# squareinator2.net
KiCad netlist of a schematic drawn in EAGLE
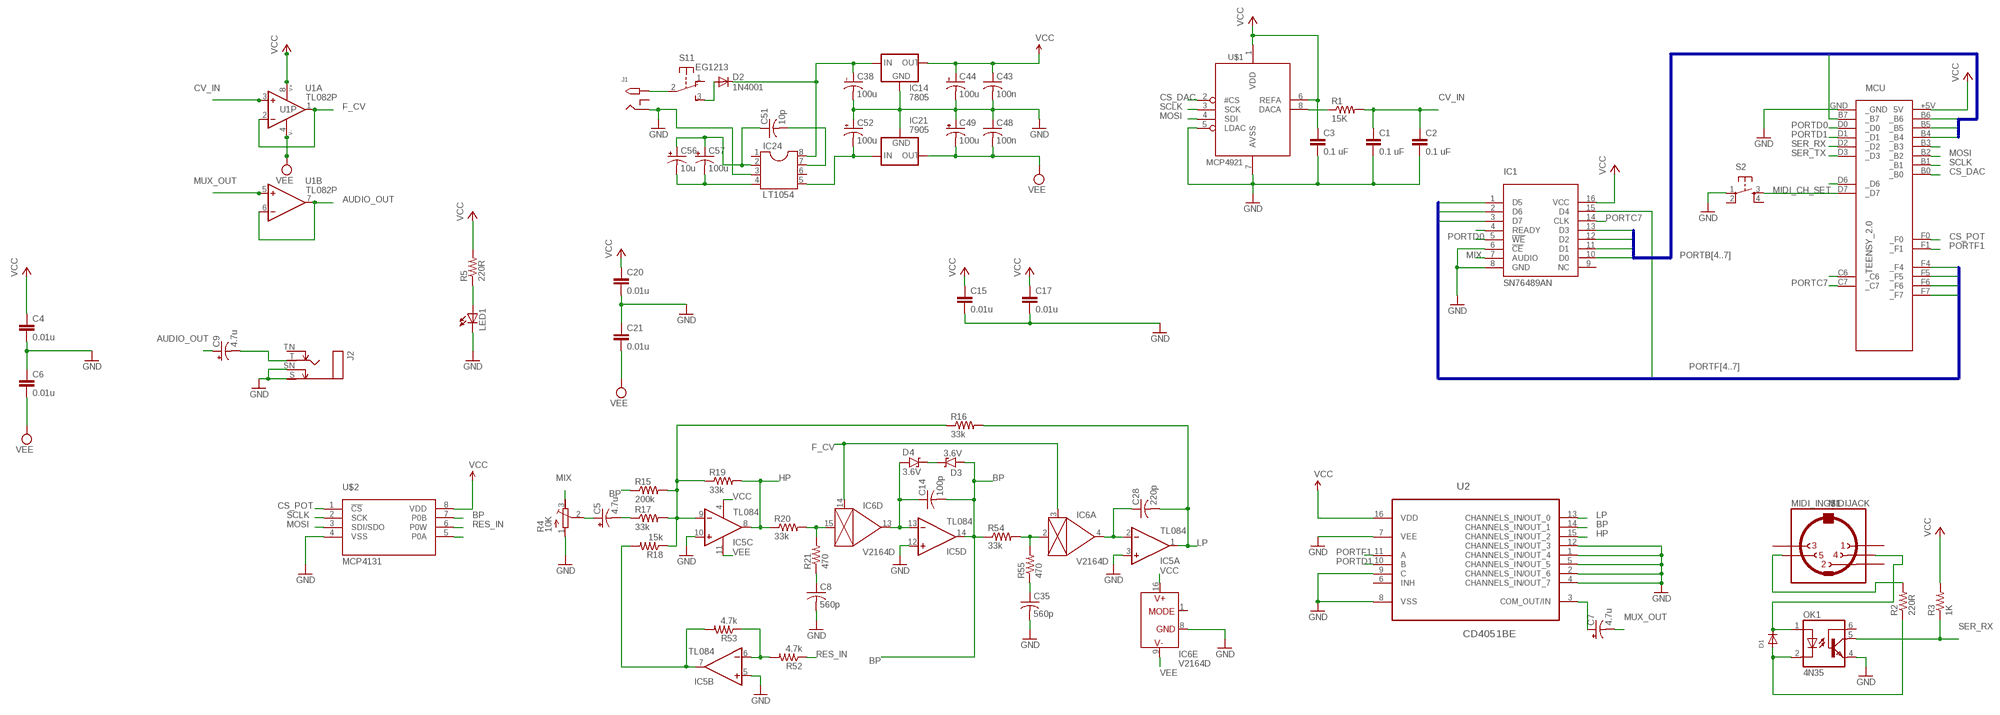
[diagram p0: schematic, sheet 1]

(export (version "E")
  (design (tool "Eeschema 10.0.6"))
  (components
    (comp (ref "C1")
      (value "0.1 uF")
      (footprint "eagle-import:CAP-PTH-SMALLEZ")
      (libsource (lib "eagle-import") (part "CAPEZ"))
    )
    (comp (ref "C2")
      (value "0.1 uF")
      (footprint "eagle-import:CAP-PTH-SMALLEZ")
      (libsource (lib "eagle-import") (part "CAPEZ"))
    )
    (comp (ref "C3")
      (value "0.1 uF")
      (footprint "eagle-import:CAP-PTH-SMALLEZ")
      (libsource (lib "eagle-import") (part "CAPEZ"))
    )
    (comp (ref "C4")
      (value "0.01u")
      (footprint "eagle-import:CAP-PTH-SMALLEZ")
      (libsource (lib "eagle-import") (part "SparkFun-Passives_CAPEZ"))
    )
    (comp (ref "C5")
      (value "4.7u")
      (footprint "eagle-import:E2,5-6")
      (libsource (lib "eagle-import") (part "CPOL-USE2.5-6"))
    )
    (comp (ref "C6")
      (value "0.01u")
      (footprint "eagle-import:CAP-PTH-SMALLEZ")
      (libsource (lib "eagle-import") (part "SparkFun-Passives_CAPEZ"))
    )
    (comp (ref "C7")
      (value "4.7u")
      (footprint "eagle-import:E2,5-6")
      (libsource (lib "eagle-import") (part "CPOL-USE2.5-6"))
    )
    (comp (ref "C8")
      (value "560p")
      (footprint "eagle-import:C025-025X050")
      (libsource (lib "eagle-import") (part "C-US025-025X050"))
    )
    (comp (ref "C9")
      (value "4.7u")
      (footprint "eagle-import:E2,5-6")
      (libsource (lib "eagle-import") (part "CPOL-USE2.5-6"))
    )
    (comp (ref "C14")
      (value "100p")
      (footprint "eagle-import:C025-025X050")
      (libsource (lib "eagle-import") (part "C-US025-025X050"))
    )
    (comp (ref "C15")
      (value "0.01u")
      (footprint "eagle-import:CAP-PTH-SMALLEZ")
      (libsource (lib "eagle-import") (part "SparkFun-Passives_CAPEZ"))
    )
    (comp (ref "C17")
      (value "0.01u")
      (footprint "eagle-import:CAP-PTH-SMALLEZ")
      (libsource (lib "eagle-import") (part "SparkFun-Passives_CAPEZ"))
    )
    (comp (ref "C20")
      (value "0.01u")
      (footprint "eagle-import:CAP-PTH-SMALLEZ")
      (libsource (lib "eagle-import") (part "SparkFun-Passives_CAPEZ"))
    )
    (comp (ref "C21")
      (value "0.01u")
      (footprint "eagle-import:CAP-PTH-SMALLEZ")
      (libsource (lib "eagle-import") (part "SparkFun-Passives_CAPEZ"))
    )
    (comp (ref "C28")
      (value "220p")
      (footprint "eagle-import:C025-025X050")
      (libsource (lib "eagle-import") (part "C-US025-025X050"))
    )
    (comp (ref "C35")
      (value "560p")
      (footprint "eagle-import:C025-025X050")
      (libsource (lib "eagle-import") (part "C-US025-025X050"))
    )
    (comp (ref "C38")
      (value "100u")
      (footprint "eagle-import:E2,5-7")
      (libsource (lib "eagle-import") (part "CPOL-USE2.5-7"))
    )
    (comp (ref "C43")
      (value "100n")
      (footprint "eagle-import:C025-025X050")
      (libsource (lib "eagle-import") (part "C-US025-025X050"))
    )
    (comp (ref "C44")
      (value "100u")
      (footprint "eagle-import:E2,5-7")
      (libsource (lib "eagle-import") (part "CPOL-USE2.5-7"))
    )
    (comp (ref "C48")
      (value "100n")
      (footprint "eagle-import:C025-025X050")
      (libsource (lib "eagle-import") (part "C-US025-025X050"))
    )
    (comp (ref "C49")
      (value "100u")
      (footprint "eagle-import:E2,5-7")
      (libsource (lib "eagle-import") (part "CPOL-USE2.5-7"))
    )
    (comp (ref "C51")
      (value "10p")
      (footprint "eagle-import:C025-025X050")
      (libsource (lib "eagle-import") (part "C-US025-025X050"))
    )
    (comp (ref "C52")
      (value "100u")
      (footprint "eagle-import:E2,5-7")
      (libsource (lib "eagle-import") (part "CPOL-USE2.5-7"))
    )
    (comp (ref "C56")
      (value "10u")
      (footprint "eagle-import:E2,5-5")
      (libsource (lib "eagle-import") (part "CPOL-USE2.5-5"))
    )
    (comp (ref "C57")
      (value "100u")
      (footprint "eagle-import:E2,5-6")
      (libsource (lib "eagle-import") (part "CPOL-USE2.5-6"))
    )
    (comp (ref "D1")
      (value "DIODEDO-1N4148")
      (footprint "eagle-import:DO-1N4148")
      (libsource (lib "eagle-import") (part "DIODEDO-1N4148"))
    )
    (comp (ref "D2")
      (value "1N4001")
      (footprint "eagle-import:DO41-10")
      (libsource (lib "eagle-import") (part "1N4004"))
    )
    (comp (ref "D3")
      (value "3.6V")
      (footprint "eagle-import:D-5")
      (libsource (lib "eagle-import") (part "1N47XXDO35"))
    )
    (comp (ref "D4")
      (value "3.6V")
      (footprint "eagle-import:D-5")
      (libsource (lib "eagle-import") (part "1N47XXDO35"))
    )
    (comp (ref "IC1")
      (value "SN76489AN")
      (footprint "eagle-import:DIL16")
      (libsource (lib "eagle-import") (part "SN76489AN"))
    )
    (comp (ref "IC5")
      (value "TL084")
      (footprint "eagle-import:DIL14")
      (libsource (lib "eagle-import") (part "TL084P"))
    )
    (comp (ref "IC6")
      (value "V2164D")
      (footprint "eagle-import:DIL16")
      (libsource (lib "eagle-import") (part "SSM2164P"))
    )
    (comp (ref "IC14")
      (value "7805")
      (footprint "eagle-import:78XXS")
      (libsource (lib "eagle-import") (part "78XXS"))
    )
    (comp (ref "IC21")
      (value "7905")
      (footprint "eagle-import:79XXS")
      (libsource (lib "eagle-import") (part "79XXS"))
    )
    (comp (ref "IC24")
      (value "LT1054")
      (footprint "eagle-import:DIL08")
      (libsource (lib "eagle-import") (part "DIL8"))
    )
    (comp (ref "J1")
      (value "2.1MMJACKTHM")
      (footprint "eagle-import:PJ-102A")
      (libsource (lib "eagle-import") (part "2.1MMJACKTHM"))
    )
    (comp (ref "J2")
      (value "MONOSWS")
      (footprint "eagle-import:NMJ4HC-S")
      (libsource (lib "eagle-import") (part "MONOSWS"))
    )
    (comp (ref "LED1")
      (value "LED3MM")
      (footprint "eagle-import:LED3MM")
      (libsource (lib "eagle-import") (part "LED3MM"))
    )
    (comp (ref "MCU")
      (value "TEENSY_2.0")
      (footprint "eagle-import:TEENSY")
      (libsource (lib "eagle-import") (part "TEENSYTEENSY_LESSPINS"))
    )
    (comp (ref "MIDI_IN")
      (value "MIDIJACK")
      (footprint "eagle-import:CP-2350")
      (libsource (lib "eagle-import") (part "MIDIJACK"))
    )
    (comp (ref "OK1")
      (value "4N35")
      (footprint "eagle-import:DIL06")
      (fields (field (name "MF") "FAIRCHILD SEMICONDUCTOR"))
      (libsource (lib "eagle-import") (part "4N35"))
    )
    (comp (ref "R1")
      (value "15K")
      (footprint "eagle-import:AXIAL-0.3EZ")
      (libsource (lib "eagle-import") (part "RESISTOREZ"))
    )
    (comp (ref "R2")
      (value "220R")
      (footprint "eagle-import:AXIAL-0.3EZ")
      (libsource (lib "eagle-import") (part "RESISTOREZ"))
    )
    (comp (ref "R3")
      (value "1K")
      (footprint "eagle-import:AXIAL-0.3EZ")
      (libsource (lib "eagle-import") (part "RESISTOREZ"))
    )
    (comp (ref "R4")
      (value "10K")
      (footprint "eagle-import:RTRIM3296P")
      (libsource (lib "eagle-import") (part "R-TRIMM3296P"))
    )
    (comp (ref "R5")
      (value "220R")
      (footprint "eagle-import:AXIAL-0.3EZ")
      (libsource (lib "eagle-import") (part "RESISTOREZ"))
    )
    (comp (ref "R15")
      (value "200k")
      (footprint "eagle-import:0204_7")
      (libsource (lib "eagle-import") (part "R-US_0204/7"))
    )
    (comp (ref "R16")
      (value "33k")
      (footprint "eagle-import:0204_7")
      (libsource (lib "eagle-import") (part "R-US_0204/7"))
    )
    (comp (ref "R17")
      (value "33k")
      (footprint "eagle-import:0204_7")
      (libsource (lib "eagle-import") (part "R-US_0204/7"))
    )
    (comp (ref "R18")
      (value "15k")
      (footprint "eagle-import:0204_7")
      (libsource (lib "eagle-import") (part "R-US_0204/7"))
    )
    (comp (ref "R19")
      (value "33k")
      (footprint "eagle-import:0204_7")
      (libsource (lib "eagle-import") (part "R-US_0204/7"))
    )
    (comp (ref "R20")
      (value "33k")
      (footprint "eagle-import:0204_7")
      (libsource (lib "eagle-import") (part "R-US_0204/7"))
    )
    (comp (ref "R21")
      (value "470")
      (footprint "eagle-import:0204_7")
      (libsource (lib "eagle-import") (part "R-US_0204/7"))
    )
    (comp (ref "R52")
      (value "4.7k")
      (footprint "eagle-import:0204_7")
      (libsource (lib "eagle-import") (part "R-US_0204/7"))
    )
    (comp (ref "R53")
      (value "4.7k")
      (footprint "eagle-import:0204_7")
      (libsource (lib "eagle-import") (part "R-US_0204/7"))
    )
    (comp (ref "R54")
      (value "33k")
      (footprint "eagle-import:0204_7")
      (libsource (lib "eagle-import") (part "R-US_0204/7"))
    )
    (comp (ref "R55")
      (value "470")
      (footprint "eagle-import:0204_7")
      (libsource (lib "eagle-import") (part "R-US_0204/7"))
    )
    (comp (ref "S1")
      (value "EG1213")
      (footprint "eagle-import:EG1213")
      (libsource (lib "eagle-import") (part "EG1213"))
    )
    (comp (ref "S2")
      (value "TAC_SWITCHPTH")
      (footprint "eagle-import:TACTILE-PTH")
      (libsource (lib "eagle-import") (part "TAC_SWITCHPTH"))
    )
    (comp (ref "U$1")
      (value "MCP4921")
      (footprint "eagle-import:DIL08")
      (libsource (lib "eagle-import") (part "MCP4921"))
    )
    (comp (ref "U$2")
      (value "MCP4131")
      (footprint "eagle-import:DIL8")
      (libsource (lib "eagle-import") (part "MCP4131"))
    )
    (comp (ref "U1")
      (value "TL082P")
      (footprint "eagle-import:DIL08")
      (libsource (lib "eagle-import") (part "TL082P"))
    )
    (comp (ref "U2")
      (value "CD4051BE")
      (footprint "eagle-import:DIP254P762X508-16")
      (libsource (lib "eagle-import") (part "CD4051BE"))
    )
  )
  (nets
    (net (code "1") (name "/AUDIO_OUT") (class "Default")
      (node (ref "C9") (pin "+") (pinfunction "+_+") (pintype "passive"))
      (node (ref "U1") (pin "6") (pinfunction "-IN_6") (pintype "input"))
      (node (ref "U1") (pin "7") (pinfunction "OUT_7") (pintype "output"))
    )
    (net (code "2") (name "/BP") (class "Default")
      (node (ref "C14") (pin "2") (pinfunction "2_2") (pintype "passive"))
      (node (ref "D3") (pin "A") (pinfunction "A_A") (pintype "passive"))
      (node (ref "IC5") (pin "14") (pinfunction "OUT_14") (pintype "output"))
      (node (ref "R15") (pin "1") (pinfunction "1_1") (pintype "passive"))
      (node (ref "R54") (pin "1") (pinfunction "1_1") (pintype "passive"))
      (node (ref "U$2") (pin "7") (pinfunction "P0B_7") (pintype "bidirectional"))
      (node (ref "U2") (pin "14") (pinfunction "CHANNELS_IN/OUT_1_14") (pintype "bidirectional"))
    )
    (net (code "3") (name "/CS_DAC") (class "Default")
      (node (ref "MCU") (pin "B0") (pinfunction "_B0_B0") (pintype "bidirectional"))
      (node (ref "U$1") (pin "2") (pinfunction "#CS_2") (pintype "input"))
    )
    (net (code "4") (name "/CS_POT") (class "Default")
      (node (ref "MCU") (pin "F0") (pinfunction "_F0_F0") (pintype "bidirectional"))
      (node (ref "U$2") (pin "1") (pinfunction "~{CS}_1") (pintype "input"))
    )
    (net (code "5") (name "/CV_IN") (class "Default")
      (node (ref "C1") (pin "1") (pinfunction "1_1") (pintype "passive"))
      (node (ref "C2") (pin "1") (pinfunction "1_1") (pintype "passive"))
      (node (ref "R1") (pin "P$2") (pinfunction "2_P$2") (pintype "passive"))
      (node (ref "U1") (pin "3") (pinfunction "+IN_3") (pintype "input"))
    )
    (net (code "6") (name "/F_CV") (class "Default")
      (node (ref "IC6") (pin "14") (pinfunction "CTRL_14") (pintype "input"))
      (node (ref "IC6") (pin "3") (pinfunction "CTRL_3") (pintype "input"))
      (node (ref "U1") (pin "1") (pinfunction "OUT_1") (pintype "output"))
      (node (ref "U1") (pin "2") (pinfunction "-IN_2") (pintype "input"))
    )
    (net (code "7") (name "/HP") (class "Default")
      (node (ref "IC5") (pin "8") (pinfunction "OUT_8") (pintype "output"))
      (node (ref "R19") (pin "2") (pinfunction "2_2") (pintype "passive"))
      (node (ref "R20") (pin "1") (pinfunction "1_1") (pintype "passive"))
      (node (ref "U2") (pin "15") (pinfunction "CHANNELS_IN/OUT_2_15") (pintype "bidirectional"))
    )
    (net (code "8") (name "/LP") (class "Default")
      (node (ref "C28") (pin "2") (pinfunction "2_2") (pintype "passive"))
      (node (ref "IC5") (pin "1") (pinfunction "OUT_1") (pintype "output"))
      (node (ref "R16") (pin "2") (pinfunction "2_2") (pintype "passive"))
      (node (ref "U2") (pin "13") (pinfunction "CHANNELS_IN/OUT_0_13") (pintype "bidirectional"))
    )
    (net (code "9") (name "/MIDI_CH_SET") (class "Default")
      (node (ref "MCU") (pin "D7") (pinfunction "_D7_D7") (pintype "bidirectional"))
      (node (ref "S2") (pin "3") (pinfunction "3_3") (pintype "passive"))
    )
    (net (code "10") (name "/MIX") (class "Default")
      (node (ref "IC1") (pin "7") (pinfunction "AUDIO_7") (pintype "output"))
      (node (ref "R4") (pin "3") (pinfunction "E_3") (pintype "passive"))
    )
    (net (code "11") (name "/MOSI") (class "Default")
      (node (ref "MCU") (pin "B2") (pinfunction "_B2_B2") (pintype "bidirectional"))
      (node (ref "U$1") (pin "4") (pinfunction "SDI_4") (pintype "input"))
      (node (ref "U$2") (pin "3") (pinfunction "SDI/SDO_3") (pintype "bidirectional"))
    )
    (net (code "12") (name "/MUX_OUT") (class "Default")
      (node (ref "C7") (pin "-") (pinfunction "-_-") (pintype "passive"))
      (node (ref "U1") (pin "5") (pinfunction "+IN_5") (pintype "input"))
    )
    (net (code "13") (name "/PORTB4") (class "Default")
      (node (ref "IC1") (pin "10") (pinfunction "D0_10") (pintype "input"))
      (node (ref "MCU") (pin "B4") (pinfunction "_B4_B4") (pintype "bidirectional"))
    )
    (net (code "14") (name "/PORTB5") (class "Default")
      (node (ref "IC1") (pin "11") (pinfunction "D1_11") (pintype "input"))
      (node (ref "MCU") (pin "B5") (pinfunction "_B5_B5") (pintype "bidirectional"))
    )
    (net (code "15") (name "/PORTB6") (class "Default")
      (node (ref "IC1") (pin "12") (pinfunction "D2_12") (pintype "input"))
      (node (ref "MCU") (pin "B6") (pinfunction "_B6_B6") (pintype "bidirectional"))
    )
    (net (code "16") (name "/PORTB7") (class "Default")
      (node (ref "IC1") (pin "13") (pinfunction "D3_13") (pintype "input"))
      (node (ref "MCU") (pin "B7") (pinfunction "_B7_B7") (pintype "bidirectional"))
    )
    (net (code "18") (name "/PORTC7") (class "Default")
      (node (ref "IC1") (pin "14") (pinfunction "CLK_14") (pintype "input"))
      (node (ref "MCU") (pin "C7") (pinfunction "_C7_C7") (pintype "bidirectional"))
    )
    (net (code "19") (name "/PORTD0") (class "Default")
      (node (ref "IC1") (pin "5") (pinfunction "~{WE}_5") (pintype "input"))
      (node (ref "MCU") (pin "D0") (pinfunction "_D0_D0") (pintype "bidirectional"))
    )
    (net (code "20") (name "/PORTD1") (class "Default")
      (node (ref "MCU") (pin "D1") (pinfunction "_D1_D1") (pintype "bidirectional"))
      (node (ref "U2") (pin "10") (pinfunction "B_10") (pintype "input"))
    )
    (net (code "21") (name "/PORTF1") (class "Default")
      (node (ref "MCU") (pin "F1") (pinfunction "_F1_F1") (pintype "bidirectional"))
      (node (ref "U2") (pin "11") (pinfunction "A_11") (pintype "input"))
    )
    (net (code "22") (name "/PORTF4") (class "Default")
      (node (ref "IC1") (pin "15") (pinfunction "D4_15") (pintype "input"))
      (node (ref "MCU") (pin "F4") (pinfunction "_F4_F4") (pintype "bidirectional"))
    )
    (net (code "23") (name "/PORTF5") (class "Default")
      (node (ref "IC1") (pin "1") (pinfunction "D5_1") (pintype "input"))
      (node (ref "MCU") (pin "F5") (pinfunction "_F5_F5") (pintype "bidirectional"))
    )
    (net (code "24") (name "/PORTF6") (class "Default")
      (node (ref "IC1") (pin "2") (pinfunction "D6_2") (pintype "input"))
      (node (ref "MCU") (pin "F6") (pinfunction "_F6_F6") (pintype "bidirectional"))
    )
    (net (code "25") (name "/PORTF7") (class "Default")
      (node (ref "IC1") (pin "3") (pinfunction "D7_3") (pintype "input"))
      (node (ref "MCU") (pin "F7") (pinfunction "_F7_F7") (pintype "bidirectional"))
    )
    (net (code "27") (name "/RES_IN") (class "Default")
      (node (ref "R52") (pin "1") (pinfunction "1_1") (pintype "passive"))
      (node (ref "U$2") (pin "6") (pinfunction "P0W_6") (pintype "bidirectional"))
    )
    (net (code "28") (name "/SCLK") (class "Default")
      (node (ref "MCU") (pin "B1") (pinfunction "_B1_B1") (pintype "bidirectional"))
      (node (ref "U$1") (pin "3") (pinfunction "SCK_3") (pintype "input"))
      (node (ref "U$2") (pin "2") (pinfunction "SCK_2") (pintype "input"))
    )
    (net (code "29") (name "/SER_RX") (class "Default")
      (node (ref "MCU") (pin "D2") (pinfunction "_D2_D2") (pintype "bidirectional"))
      (node (ref "OK1") (pin "5") (pinfunction "COL_5") (pintype "passive"))
      (node (ref "R3") (pin "P$1") (pinfunction "1_P$1") (pintype "passive"))
    )
    (net (code "30") (name "/SER_TX") (class "Default")
      (node (ref "MCU") (pin "D3") (pinfunction "_D3_D3") (pintype "bidirectional"))
    )
    (net (code "31") (name "GND") (class "Default")
      (node (ref "C1") (pin "2") (pinfunction "2_2") (pintype "passive"))
      (node (ref "C15") (pin "2") (pinfunction "2_2") (pintype "passive"))
      (node (ref "C17") (pin "2") (pinfunction "2_2") (pintype "passive"))
      (node (ref "C2") (pin "2") (pinfunction "2_2") (pintype "passive"))
      (node (ref "C20") (pin "2") (pinfunction "2_2") (pintype "passive"))
      (node (ref "C21") (pin "1") (pinfunction "1_1") (pintype "passive"))
      (node (ref "C3") (pin "2") (pinfunction "2_2") (pintype "passive"))
      (node (ref "C35") (pin "2") (pinfunction "2_2") (pintype "passive"))
      (node (ref "C38") (pin "-") (pinfunction "-_-") (pintype "passive"))
      (node (ref "C4") (pin "2") (pinfunction "2_2") (pintype "passive"))
      (node (ref "C43") (pin "2") (pinfunction "2_2") (pintype "passive"))
      (node (ref "C44") (pin "-") (pinfunction "-_-") (pintype "passive"))
      (node (ref "C48") (pin "1") (pinfunction "1_1") (pintype "passive"))
      (node (ref "C49") (pin "+") (pinfunction "+_+") (pintype "passive"))
      (node (ref "C52") (pin "+") (pinfunction "+_+") (pintype "passive"))
      (node (ref "C6") (pin "1") (pinfunction "1_1") (pintype "passive"))
      (node (ref "C8") (pin "2") (pinfunction "2_2") (pintype "passive"))
      (node (ref "IC1") (pin "6") (pinfunction "~{CE}_6") (pintype "input"))
      (node (ref "IC1") (pin "8") (pinfunction "GND_8") (pintype "power_in"))
      (node (ref "IC14") (pin "GND") (pinfunction "GND_GND") (pintype "input"))
      (node (ref "IC21") (pin "GND") (pinfunction "GND_GND") (pintype "input"))
      (node (ref "IC24") (pin "3") (pinfunction "3_3") (pintype "passive"))
      (node (ref "IC5") (pin "10") (pinfunction "+IN_10") (pintype "input"))
      (node (ref "IC5") (pin "12") (pinfunction "+IN_12") (pintype "input"))
      (node (ref "IC5") (pin "3") (pinfunction "+IN_3") (pintype "input"))
      (node (ref "IC5") (pin "5") (pinfunction "+IN_5") (pintype "input"))
      (node (ref "IC6") (pin "8") (pinfunction "GND_8") (pintype "power_in"))
      (node (ref "J1") (pin "RING") (pinfunction "RING_RING") (pintype "bidirectional"))
      (node (ref "J2") (pin "S") (pinfunction "S_S") (pintype "passive"))
      (node (ref "J2") (pin "SN") (pinfunction "SN_SN") (pintype "passive"))
      (node (ref "LED1") (pin "K") (pinfunction "C_K") (pintype "passive"))
      (node (ref "MCU") (pin "GND") (pinfunction "_GND_GND") (pintype "bidirectional"))
      (node (ref "OK1") (pin "4") (pinfunction "EMI_4") (pintype "passive"))
      (node (ref "R4") (pin "1") (pinfunction "A_1") (pintype "passive"))
      (node (ref "S2") (pin "1") (pinfunction "1_1") (pintype "passive"))
      (node (ref "U$1") (pin "5") (pinfunction "LDAC_5") (pintype "input"))
      (node (ref "U$1") (pin "7") (pinfunction "AVSS_7") (pintype "power_in"))
      (node (ref "U$2") (pin "4") (pinfunction "VSS_4") (pintype "power_in"))
      (node (ref "U2") (pin "1") (pinfunction "CHANNELS_IN/OUT_4_1") (pintype "bidirectional"))
      (node (ref "U2") (pin "12") (pinfunction "CHANNELS_IN/OUT_3_12") (pintype "bidirectional"))
      (node (ref "U2") (pin "2") (pinfunction "CHANNELS_IN/OUT_6_2") (pintype "bidirectional"))
      (node (ref "U2") (pin "4") (pinfunction "CHANNELS_IN/OUT_7_4") (pintype "bidirectional"))
      (node (ref "U2") (pin "5") (pinfunction "CHANNELS_IN/OUT_5_5") (pintype "bidirectional"))
      (node (ref "U2") (pin "7") (pinfunction "VEE_7") (pintype "power_in"))
      (node (ref "U2") (pin "8") (pinfunction "VSS_8") (pintype "power_in"))
      (node (ref "U2") (pin "9") (pinfunction "C_9") (pintype "input"))
    )
    (net (code "32") (name "Net-(C5-Pad-)") (class "Default")
      (node (ref "C5") (pin "-") (pinfunction "-_-") (pintype "passive"))
      (node (ref "R17") (pin "1") (pinfunction "1_1") (pintype "passive"))
    )
    (net (code "33") (name "Net-(C8-Pad1)") (class "Default")
      (node (ref "C8") (pin "1") (pinfunction "1_1") (pintype "passive"))
      (node (ref "R21") (pin "1") (pinfunction "1_1") (pintype "passive"))
    )
    (net (code "34") (name "Net-(C9-Pad-)") (class "Default")
      (node (ref "C9") (pin "-") (pinfunction "-_-") (pintype "passive"))
      (node (ref "J2") (pin "T") (pinfunction "T_T") (pintype "passive"))
    )
    (net (code "35") (name "Net-(C35-Pad1)") (class "Default")
      (node (ref "C35") (pin "1") (pinfunction "1_1") (pintype "passive"))
      (node (ref "R55") (pin "1") (pinfunction "1_1") (pintype "passive"))
    )
    (net (code "36") (name "Net-(C38-Pad+)") (class "Default")
      (node (ref "C38") (pin "+") (pinfunction "+_+") (pintype "passive"))
      (node (ref "D2") (pin "C") (pinfunction "C_C") (pintype "passive"))
      (node (ref "IC14") (pin "IN") (pinfunction "IN_IN") (pintype "input"))
      (node (ref "IC24") (pin "8") (pinfunction "8_8") (pintype "passive"))
    )
    (net (code "37") (name "Net-(C51-Pad1)") (class "Default")
      (node (ref "C51") (pin "1") (pinfunction "1_1") (pintype "passive"))
      (node (ref "C56") (pin "+") (pinfunction "+_+") (pintype "passive"))
      (node (ref "C57") (pin "+") (pinfunction "+_+") (pintype "passive"))
      (node (ref "IC24") (pin "2") (pinfunction "2_2") (pintype "passive"))
    )
    (net (code "38") (name "Net-(C51-Pad2)") (class "Default")
      (node (ref "C51") (pin "2") (pinfunction "2_2") (pintype "passive"))
      (node (ref "IC24") (pin "7") (pinfunction "7_7") (pintype "passive"))
    )
    (net (code "39") (name "Net-(C52-Pad-)") (class "Default")
      (node (ref "C52") (pin "-") (pinfunction "-_-") (pintype "passive"))
      (node (ref "IC21") (pin "IN") (pinfunction "IN_IN") (pintype "input"))
      (node (ref "IC24") (pin "5") (pinfunction "5_5") (pintype "passive"))
    )
    (net (code "40") (name "Net-(C56-Pad-)") (class "Default")
      (node (ref "C56") (pin "-") (pinfunction "-_-") (pintype "passive"))
      (node (ref "C57") (pin "-") (pinfunction "-_-") (pintype "passive"))
      (node (ref "IC24") (pin "4") (pinfunction "4_4") (pintype "passive"))
    )
    (net (code "41") (name "Net-(D3-PadC)") (class "Default")
      (node (ref "D3") (pin "C") (pinfunction "C_C") (pintype "passive"))
      (node (ref "D4") (pin "C") (pinfunction "C_C") (pintype "passive"))
    )
    (net (code "42") (name "Net-(IC5A--IN)") (class "Default")
      (node (ref "C28") (pin "1") (pinfunction "1_1") (pintype "passive"))
      (node (ref "IC5") (pin "2") (pinfunction "-IN_2") (pintype "input"))
      (node (ref "IC6") (pin "4") (pinfunction "OUT_4") (pintype "output"))
    )
    (net (code "43") (name "Net-(IC5B--IN)") (class "Default")
      (node (ref "IC5") (pin "6") (pinfunction "-IN_6") (pintype "input"))
      (node (ref "R52") (pin "2") (pinfunction "2_2") (pintype "passive"))
      (node (ref "R53") (pin "1") (pinfunction "1_1") (pintype "passive"))
    )
    (net (code "44") (name "Net-(IC5B-OUT)") (class "Default")
      (node (ref "IC5") (pin "7") (pinfunction "OUT_7") (pintype "output"))
      (node (ref "R18") (pin "2") (pinfunction "2_2") (pintype "passive"))
      (node (ref "R53") (pin "2") (pinfunction "2_2") (pintype "passive"))
    )
    (net (code "45") (name "Net-(IC5C--IN)") (class "Default")
      (node (ref "IC5") (pin "9") (pinfunction "-IN_9") (pintype "input"))
      (node (ref "R15") (pin "2") (pinfunction "2_2") (pintype "passive"))
      (node (ref "R16") (pin "1") (pinfunction "1_1") (pintype "passive"))
      (node (ref "R17") (pin "2") (pinfunction "2_2") (pintype "passive"))
      (node (ref "R18") (pin "1") (pinfunction "1_1") (pintype "passive"))
      (node (ref "R19") (pin "1") (pinfunction "1_1") (pintype "passive"))
    )
    (net (code "46") (name "Net-(IC5D--IN)") (class "Default")
      (node (ref "C14") (pin "1") (pinfunction "1_1") (pintype "passive"))
      (node (ref "D4") (pin "A") (pinfunction "A_A") (pintype "passive"))
      (node (ref "IC5") (pin "13") (pinfunction "-IN_13") (pintype "input"))
      (node (ref "IC6") (pin "13") (pinfunction "OUT_13") (pintype "output"))
    )
    (net (code "47") (name "Net-(IC6A-IN)") (class "Default")
      (node (ref "IC6") (pin "2") (pinfunction "IN_2") (pintype "input"))
      (node (ref "R54") (pin "2") (pinfunction "2_2") (pintype "passive"))
      (node (ref "R55") (pin "2") (pinfunction "2_2") (pintype "passive"))
    )
    (net (code "48") (name "Net-(IC6D-IN)") (class "Default")
      (node (ref "IC6") (pin "15") (pinfunction "IN_15") (pintype "input"))
      (node (ref "R20") (pin "2") (pinfunction "2_2") (pintype "passive"))
      (node (ref "R21") (pin "2") (pinfunction "2_2") (pintype "passive"))
    )
    (net (code "49") (name "Net-(OK1-A)") (class "Default")
      (node (ref "D1") (pin "C") (pinfunction "C_C") (pintype "passive"))
      (node (ref "MIDI_IN") (pin "4") (pinfunction "4_4") (pintype "passive"))
      (node (ref "OK1") (pin "1") (pinfunction "A_1") (pintype "passive"))
    )
    (net (code "50") (name "Net-(OK1-C)") (class "Default")
      (node (ref "D1") (pin "A") (pinfunction "A_A") (pintype "passive"))
      (node (ref "OK1") (pin "2") (pinfunction "C_2") (pintype "passive"))
      (node (ref "R2") (pin "P$1") (pinfunction "1_P$1") (pintype "passive"))
    )
    (net (code "51") (name "Net-(R1-1)") (class "Default")
      (node (ref "R1") (pin "P$1") (pinfunction "1_P$1") (pintype "passive"))
      (node (ref "U$1") (pin "8") (pinfunction "DACA_8") (pintype "output"))
    )
    (net (code "52") (name "Net-(R2-2)") (class "Default")
      (node (ref "MIDI_IN") (pin "5") (pinfunction "5_5") (pintype "passive"))
      (node (ref "R2") (pin "P$2") (pinfunction "2_P$2") (pintype "passive"))
    )
    (net (code "53") (name "Net-(R4-S)") (class "Default")
      (node (ref "C5") (pin "+") (pinfunction "+_+") (pintype "passive"))
      (node (ref "R4") (pin "2") (pinfunction "S_2") (pintype "passive"))
    )
    (net (code "54") (name "Net-(R5-1)") (class "Default")
      (node (ref "LED1") (pin "A") (pinfunction "A_A") (pintype "passive"))
      (node (ref "R5") (pin "P$1") (pinfunction "1_P$1") (pintype "passive"))
    )
    (net (code "55") (name "Net-(S1A-P)") (class "Default")
      (node (ref "J1") (pin "TIP") (pinfunction "TIP_TIP") (pintype "bidirectional"))
      (node (ref "S1") (pin "2") (pinfunction "P_2") (pintype "passive"))
    )
    (net (code "56") (name "Net-(S1A-S)") (class "Default")
      (node (ref "D2") (pin "A") (pinfunction "A_A") (pintype "passive"))
      (node (ref "S1") (pin "3") (pinfunction "S_3") (pintype "passive"))
    )
    (net (code "57") (name "Net-(U2-COM_OUT{slash}IN)") (class "Default")
      (node (ref "C7") (pin "+") (pinfunction "+_+") (pintype "passive"))
      (node (ref "U2") (pin "3") (pinfunction "COM_OUT/IN_3") (pintype "bidirectional"))
    )
    (net (code "58") (name "VCC") (class "Default")
      (node (ref "C15") (pin "1") (pinfunction "1_1") (pintype "passive"))
      (node (ref "C17") (pin "1") (pinfunction "1_1") (pintype "passive"))
      (node (ref "C20") (pin "1") (pinfunction "1_1") (pintype "passive"))
      (node (ref "C3") (pin "1") (pinfunction "1_1") (pintype "passive"))
      (node (ref "C4") (pin "1") (pinfunction "1_1") (pintype "passive"))
      (node (ref "C43") (pin "1") (pinfunction "1_1") (pintype "passive"))
      (node (ref "C44") (pin "+") (pinfunction "+_+") (pintype "passive"))
      (node (ref "IC1") (pin "16") (pinfunction "VCC_16") (pintype "input"))
      (node (ref "IC14") (pin "OUT") (pinfunction "OUT_OUT") (pintype "passive"))
      (node (ref "IC5") (pin "4") (pinfunction "V+_4") (pintype "power_in"))
      (node (ref "IC6") (pin "16") (pinfunction "V+_16") (pintype "power_in"))
      (node (ref "MCU") (pin "+5V") (pinfunction "5V_+5V") (pintype "bidirectional"))
      (node (ref "R3") (pin "P$2") (pinfunction "2_P$2") (pintype "passive"))
      (node (ref "R5") (pin "P$2") (pinfunction "2_P$2") (pintype "passive"))
      (node (ref "U$1") (pin "1") (pinfunction "VDD_1") (pintype "power_in"))
      (node (ref "U$1") (pin "6") (pinfunction "REFA_6") (pintype "input"))
      (node (ref "U$2") (pin "8") (pinfunction "VDD_8") (pintype "power_in"))
      (node (ref "U1") (pin "8") (pinfunction "V+_8") (pintype "power_in"))
      (node (ref "U2") (pin "16") (pinfunction "VDD_16") (pintype "power_in"))
    )
    (net (code "59") (name "VEE") (class "Default")
      (node (ref "C21") (pin "2") (pinfunction "2_2") (pintype "passive"))
      (node (ref "C48") (pin "2") (pinfunction "2_2") (pintype "passive"))
      (node (ref "C49") (pin "-") (pinfunction "-_-") (pintype "passive"))
      (node (ref "C6") (pin "2") (pinfunction "2_2") (pintype "passive"))
      (node (ref "IC21") (pin "OUT") (pinfunction "OUT_OUT") (pintype "passive"))
      (node (ref "IC5") (pin "11") (pinfunction "V-_11") (pintype "power_in"))
      (node (ref "IC6") (pin "9") (pinfunction "V-_9") (pintype "power_in"))
      (node (ref "U1") (pin "4") (pinfunction "V-_4") (pintype "power_in"))
    )
    (net (code "60") (name "unconnected-(IC1-NC-Pad9)") (class "Default")
      (node (ref "IC1") (pin "9") (pinfunction "NC_9") (pintype "no_connect"))
    )
    (net (code "61") (name "unconnected-(IC1-READY-Pad4)") (class "Default")
      (node (ref "IC1") (pin "4") (pinfunction "READY_4") (pintype "output"))
    )
    (net (code "62") (name "unconnected-(IC6E-MODE-Pad1)") (class "Default")
      (node (ref "IC6") (pin "1") (pinfunction "MODE_1") (pintype "input"))
    )
    (net (code "63") (name "unconnected-(IC24-Pad1)") (class "Default")
      (node (ref "IC24") (pin "1") (pinfunction "1_1") (pintype "passive"))
    )
    (net (code "64") (name "unconnected-(IC24-Pad6)") (class "Default")
      (node (ref "IC24") (pin "6") (pinfunction "6_6") (pintype "passive"))
    )
    (net (code "65") (name "unconnected-(J1-PadRING_SW)") (class "Default")
      (node (ref "J1") (pin "RING_SW") (pinfunction "RING_SW_RING_SW") (pintype "bidirectional"))
    )
    (net (code "66") (name "unconnected-(J2-PadTN)") (class "Default")
      (node (ref "J2") (pin "TN") (pinfunction "TN_TN") (pintype "passive"))
    )
    (net (code "67") (name "unconnected-(MCU-_B3-PadB3)") (class "Default")
      (node (ref "MCU") (pin "B3") (pinfunction "_B3_B3") (pintype "bidirectional"))
    )
    (net (code "68") (name "unconnected-(MCU-_C6-PadC6)") (class "Default")
      (node (ref "MCU") (pin "C6") (pinfunction "_C6_C6") (pintype "bidirectional"))
    )
    (net (code "69") (name "unconnected-(MCU-_D6-PadD6)") (class "Default")
      (node (ref "MCU") (pin "D6") (pinfunction "_D6_D6") (pintype "bidirectional"))
    )
    (net (code "70") (name "unconnected-(MIDI_IN-Pad1)") (class "Default")
      (node (ref "MIDI_IN") (pin "1") (pinfunction "1_1") (pintype "passive"))
    )
    (net (code "71") (name "unconnected-(MIDI_IN-Pad2)") (class "Default")
      (node (ref "MIDI_IN") (pin "2") (pinfunction "2_2") (pintype "passive"))
    )
    (net (code "72") (name "unconnected-(MIDI_IN-Pad3)") (class "Default")
      (node (ref "MIDI_IN") (pin "3") (pinfunction "3_3") (pintype "passive"))
    )
    (net (code "73") (name "unconnected-(OK1-BAS-Pad6)") (class "Default")
      (node (ref "OK1") (pin "6") (pinfunction "BAS_6") (pintype "passive"))
    )
    (net (code "74") (name "unconnected-(S1A-O-Pad1)") (class "Default")
      (node (ref "S1") (pin "1") (pinfunction "O_1") (pintype "passive"))
    )
    (net (code "75") (name "unconnected-(S2-Pad2)") (class "Default")
      (node (ref "S2") (pin "2") (pinfunction "2_2") (pintype "passive"))
    )
    (net (code "76") (name "unconnected-(S2-Pad4)") (class "Default")
      (node (ref "S2") (pin "4") (pinfunction "4_4") (pintype "passive"))
    )
    (net (code "77") (name "unconnected-(U$2-P0A-Pad5)") (class "Default")
      (node (ref "U$2") (pin "5") (pinfunction "P0A_5") (pintype "bidirectional"))
    )
    (net (code "78") (name "unconnected-(U2-INH-Pad6)") (class "Default")
      (node (ref "U2") (pin "6") (pinfunction "INH_6") (pintype "input"))
    )
  )
)
